# design.net
KiCad netlist of a schematic drawn in EasyEDA Pro
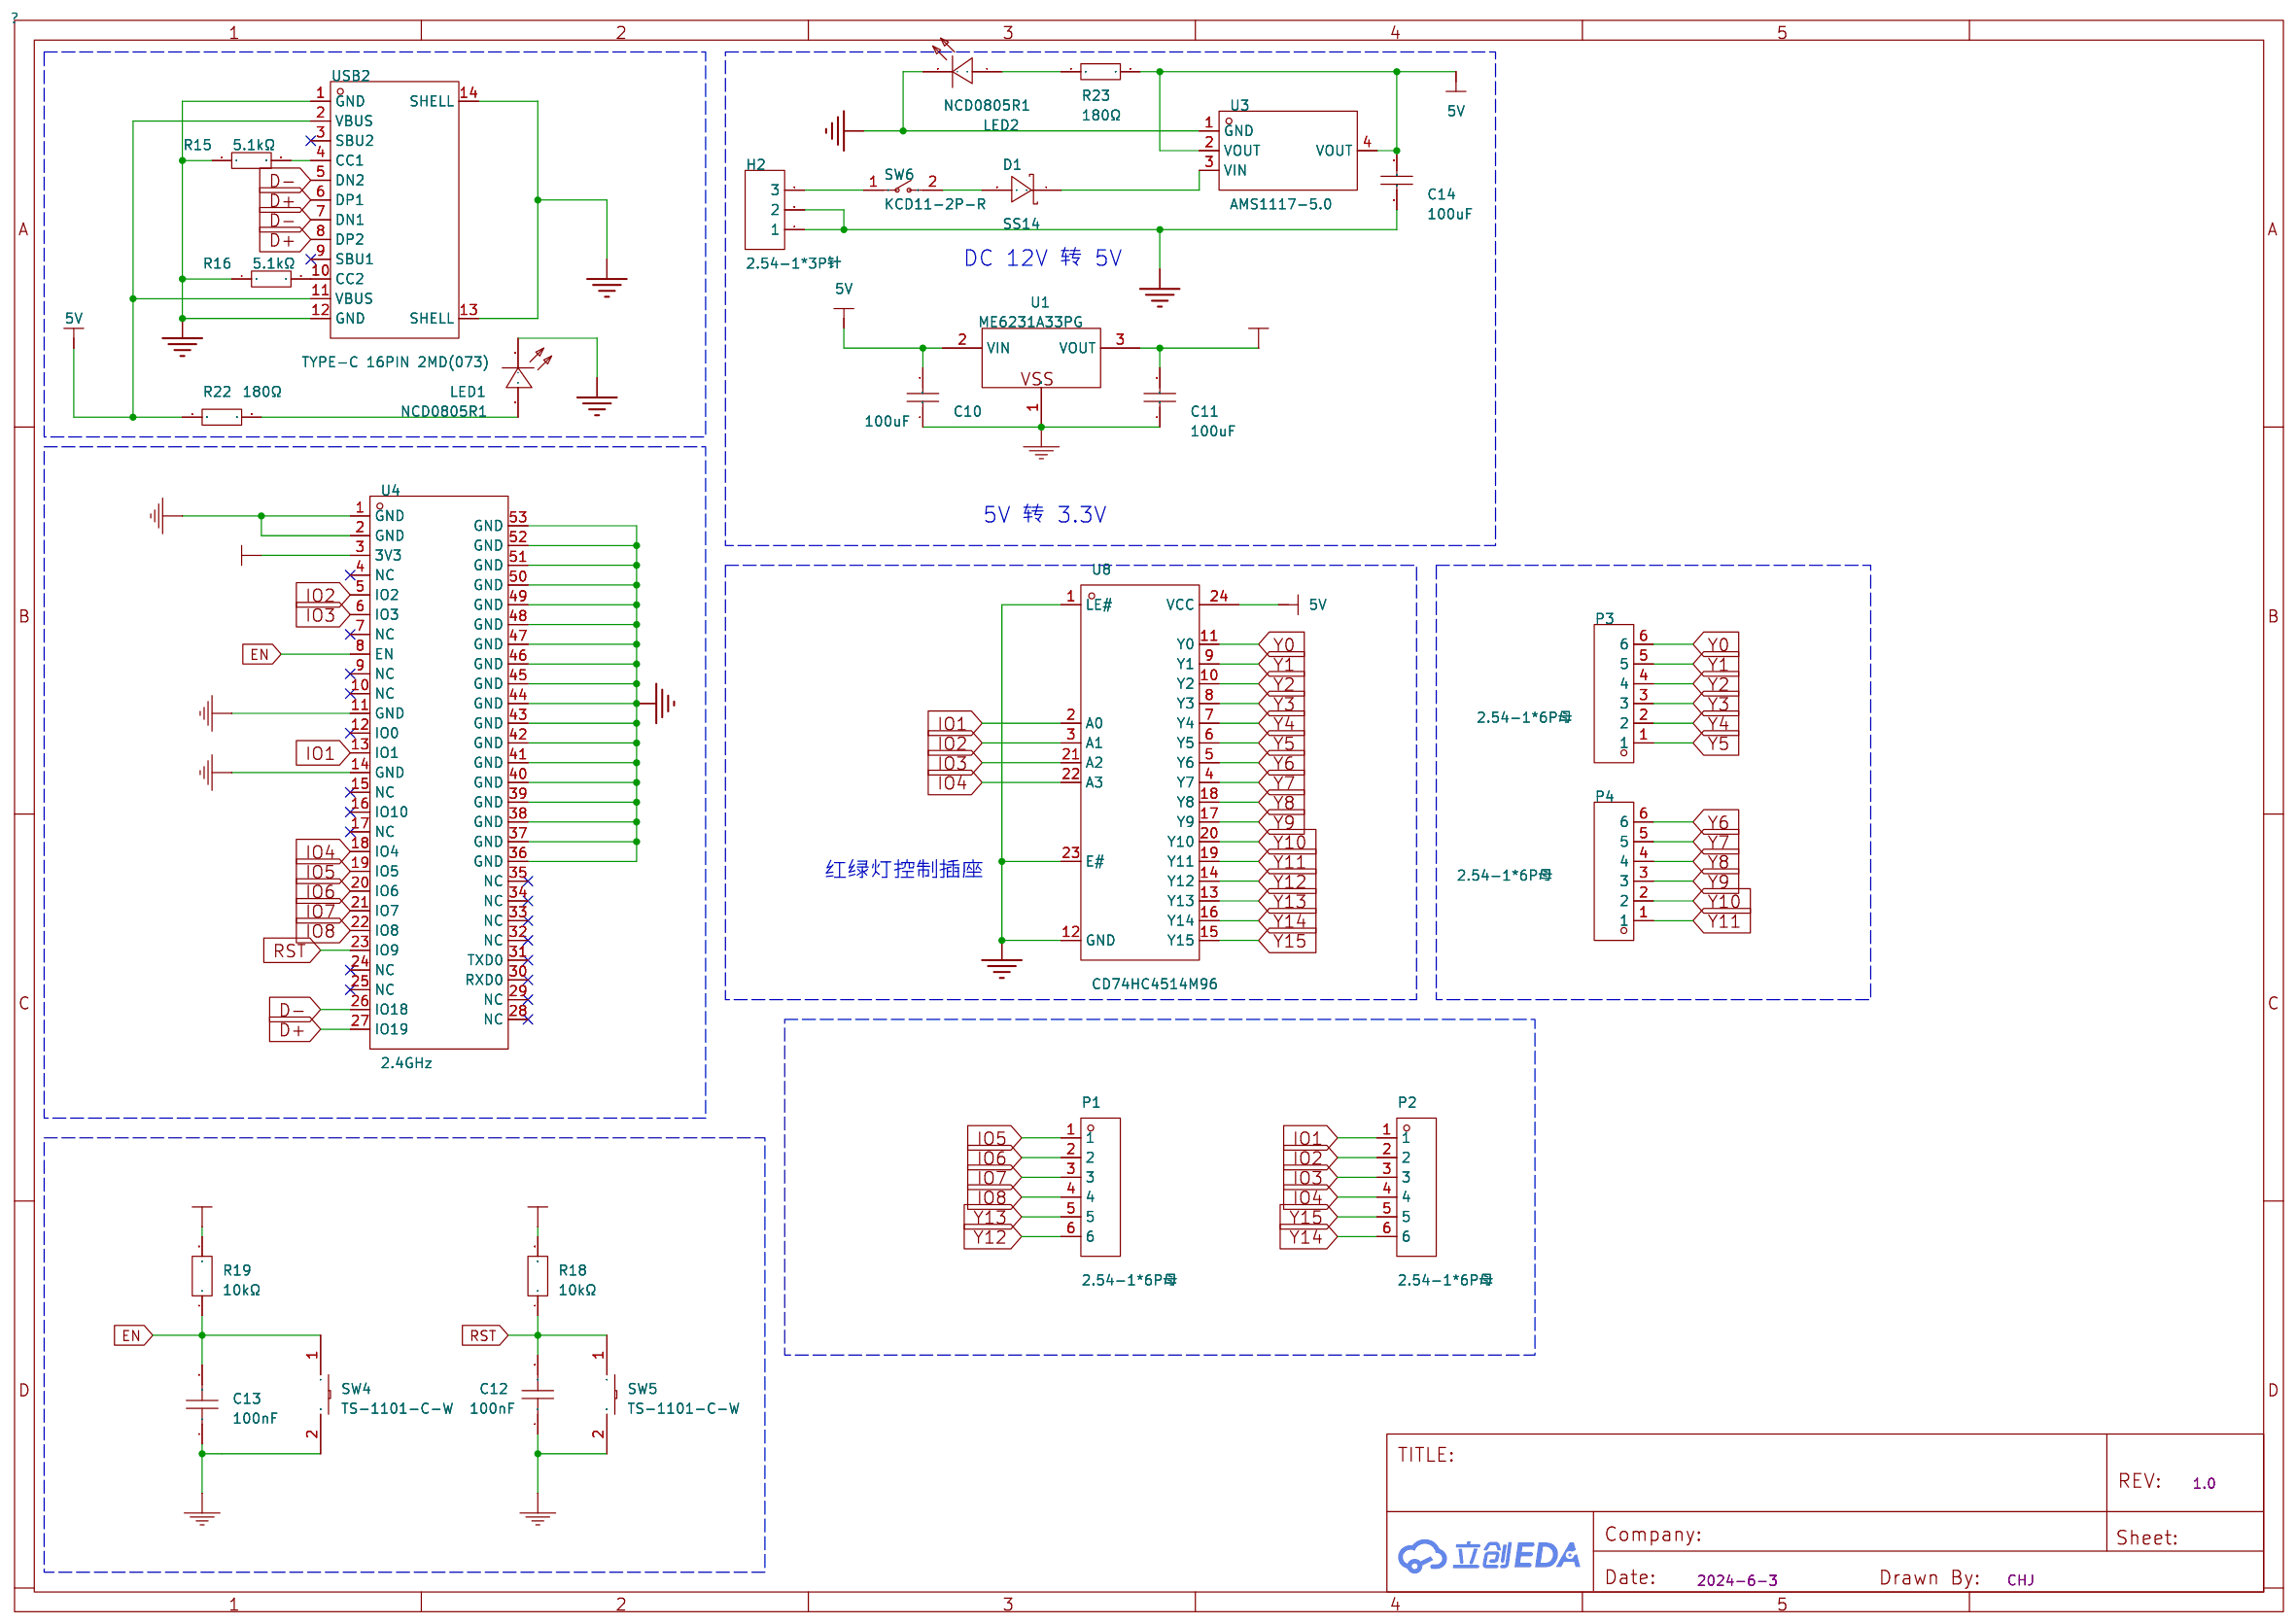
[diagram p0: schematic sheet]

(export (version "E")
  (design (tool "Eeschema 10.0.6"))
  (components
    (comp (ref "C10")
      (value "100uF")
      (footprint "easyedapro:C1206")
      (description "容值:100uF;精度:±20%;额定电压:6.3V;材质(温度系数):X5R;")
      (fields
        (field (name "Manufacturer Part") "CL31A107MQHNNNE")
        (field (name "Manufacturer") "SAMSUNG(三星)")
      )
      (libsource (lib "easyedapro") (part "CL31A107MQHNNNE"))
    )
    (comp (ref "C11")
      (value "100uF")
      (footprint "easyedapro:C1206")
      (description "容值:100uF;精度:±20%;额定电压:6.3V;材质(温度系数):X5R;")
      (fields
        (field (name "Manufacturer Part") "CL31A107MQHNNNE")
        (field (name "Manufacturer") "SAMSUNG(三星)")
      )
      (libsource (lib "easyedapro") (part "CL31A107MQHNNNE"))
    )
    (comp (ref "C12")
      (value "100nF")
      (footprint "easyedapro:C0603")
      (description "容值:100nF;精度:±10%;额定电压:50V;材质(温度系数):X7R;")
      (fields
        (field (name "Manufacturer Part") "CC0603KRX7R9BB104")
        (field (name "Manufacturer") "YAGEO(国巨)")
      )
      (libsource (lib "easyedapro") (part "CC0603KRX7R9BB104"))
    )
    (comp (ref "C13")
      (value "100nF")
      (footprint "easyedapro:C0603")
      (description "容值:100nF;精度:±10%;额定电压:50V;材质(温度系数):X7R;")
      (fields
        (field (name "Manufacturer Part") "CC0603KRX7R9BB104")
        (field (name "Manufacturer") "YAGEO(国巨)")
      )
      (libsource (lib "easyedapro") (part "CC0603KRX7R9BB104"))
    )
    (comp (ref "C14")
      (value "100uF")
      (footprint "easyedapro:C1206")
      (description "容值:100uF;精度:±20%;额定电压:6.3V;材质(温度系数):X5R;")
      (fields
        (field (name "Manufacturer Part") "CL31A107MQHNNNE")
        (field (name "Manufacturer") "SAMSUNG(三星)")
      )
      (libsource (lib "easyedapro") (part "CL31A107MQHNNNE"))
    )
    (comp (ref "D1")
      (value "SS14")
      (footprint "easyedapro:SMA_L4.2-W2.6-LS5.3-RD")
      (description "二极管配置:独立式;正向压降(Vf):550mV@1A;直流反向耐压(Vr):40V;平均整流电流(Io):1A;")
      (fields (field (name "Manufacturer") "MDD"))
      (libsource (lib "easyedapro") (part "SS14"))
    )
    (comp (ref "H2")
      (value "2.54-1*3P针")
      (footprint "easyedapro:HDR-TH_3P-P2.54-V-M-1")
      (fields (field (name "Manufacturer") "BOOMELE(博穆精密)"))
      (libsource (lib "easyedapro") (part "Header-Male-2.54_1x3"))
    )
    (comp (ref "LED1")
      (value "NCD0805R1")
      (footprint "easyedapro:LED0805-R-RD")
      (fields (field (name "Manufacturer") "国星光电"))
      (libsource (lib "easyedapro") (part "FC-2012HRK-620D"))
    )
    (comp (ref "LED2")
      (value "NCD0805R1")
      (footprint "easyedapro:LED0805-R-RD")
      (fields (field (name "Manufacturer") "国星光电"))
      (libsource (lib "easyedapro") (part "FC-2012HRK-620D"))
    )
    (comp (ref "P1")
      (value "2.54-1*6P母")
      (footprint "easyedapro:HDR-TH_6P-P2.54-V-F")
      (description "插孔结构:1x6P;间距:2.54mm;行距:-;安装类型:直插;排数:单排;总孔位数:6P;塑高:-;触头材质:-;触头镀层:-;")
      (fields (field (name "Manufacturer") "BOOMELE(博穆精密)"))
      (libsource (lib "easyedapro") (part "Header-Female-2.54_1x6"))
    )
    (comp (ref "P2")
      (value "2.54-1*6P母")
      (footprint "easyedapro:HDR-TH_6P-P2.54-V-F")
      (description "插孔结构:1x6P;间距:2.54mm;行距:-;安装类型:直插;排数:单排;总孔位数:6P;塑高:-;触头材质:-;触头镀层:-;")
      (fields (field (name "Manufacturer") "BOOMELE(博穆精密)"))
      (libsource (lib "easyedapro") (part "Header-Female-2.54_1x6"))
    )
    (comp (ref "P3")
      (value "2.54-1*6P母")
      (footprint "easyedapro:HDR-TH_6P-P2.54-V-F")
      (description "插孔结构:1x6P;间距:2.54mm;行距:-;安装类型:直插;排数:单排;总孔位数:6P;塑高:-;触头材质:-;触头镀层:-;")
      (fields (field (name "Manufacturer") "BOOMELE(博穆精密)"))
      (libsource (lib "easyedapro") (part "Header-Female-2.54_1x6"))
    )
    (comp (ref "P4")
      (value "2.54-1*6P母")
      (footprint "easyedapro:HDR-TH_6P-P2.54-V-F")
      (description "插孔结构:1x6P;间距:2.54mm;行距:-;安装类型:直插;排数:单排;总孔位数:6P;塑高:-;触头材质:-;触头镀层:-;")
      (fields (field (name "Manufacturer") "BOOMELE(博穆精密)"))
      (libsource (lib "easyedapro") (part "Header-Female-2.54_1x6"))
    )
    (comp (ref "R15")
      (value "5.1kΩ")
      (footprint "easyedapro:R0603")
      (description "电阻类型:厚膜电阻;阻值:5.1kΩ;精度:±1%;功率:100mW;最大工作电压:75V;温度系数:±100ppm/°C;")
      (fields
        (field (name "Manufacturer Part") "0603WAF5101T5E")
        (field (name "Manufacturer") "UNI-ROYAL(厚声)")
      )
      (libsource (lib "easyedapro") (part "0603WAF5101T5E"))
    )
    (comp (ref "R16")
      (value "5.1kΩ")
      (footprint "easyedapro:R0603")
      (description "电阻类型:厚膜电阻;阻值:5.1kΩ;精度:±1%;功率:100mW;最大工作电压:75V;温度系数:±100ppm/°C;")
      (fields
        (field (name "Manufacturer Part") "0603WAF5101T5E")
        (field (name "Manufacturer") "UNI-ROYAL(厚声)")
      )
      (libsource (lib "easyedapro") (part "0603WAF5101T5E"))
    )
    (comp (ref "R18")
      (value "10kΩ")
      (footprint "easyedapro:R0603")
      (description "电阻类型:厚膜电阻;阻值:10kΩ;精度:±5%;功率:100mW;最大工作电压:75V;温度系数:±100ppm/°C;")
      (fields (field (name "Manufacturer Part") "FRC0603J103TS") (field (name "Manufacturer") "FOJAN(富捷)"))
      (libsource (lib "easyedapro") (part "FRC0603J103TS"))
    )
    (comp (ref "R19")
      (value "10kΩ")
      (footprint "easyedapro:R0603")
      (description "电阻类型:厚膜电阻;阻值:10kΩ;精度:±5%;功率:100mW;最大工作电压:75V;温度系数:±100ppm/°C;")
      (fields (field (name "Manufacturer Part") "FRC0603J103TS") (field (name "Manufacturer") "FOJAN(富捷)"))
      (libsource (lib "easyedapro") (part "FRC0603J103TS"))
    )
    (comp (ref "R22")
      (value "180Ω")
      (footprint "easyedapro:R0805")
      (description "电阻类型:厚膜电阻;阻值:180Ω;精度:±1%;功率:125mW;最大工作电压:150V;温度系数:±100ppm/°C;")
      (fields
        (field (name "Manufacturer Part") "0805W8F1800T5E")
        (field (name "Manufacturer") "UNI-ROYAL(厚声)")
      )
      (libsource (lib "easyedapro") (part "0805W8F1800T5E"))
    )
    (comp (ref "R23")
      (value "180Ω")
      (footprint "easyedapro:R0805")
      (description "电阻类型:厚膜电阻;阻值:180Ω;精度:±1%;功率:125mW;最大工作电压:150V;温度系数:±100ppm/°C;")
      (fields
        (field (name "Manufacturer Part") "0805W8F1800T5E")
        (field (name "Manufacturer") "UNI-ROYAL(厚声)")
      )
      (libsource (lib "easyedapro") (part "0805W8F1800T5E"))
    )
    (comp (ref "SW4")
      (value "TS-1101-C-W")
      (footprint "easyedapro:SW-SMD_L6.0-W3.3-LS8.0")
      (fields (field (name "Manufacturer") "XKB Connectivity(中国星坤)"))
      (libsource (lib "easyedapro") (part "TS-1101-C-W"))
    )
    (comp (ref "SW5")
      (value "TS-1101-C-W")
      (footprint "easyedapro:SW-SMD_L6.0-W3.3-LS8.0")
      (fields (field (name "Manufacturer") "XKB Connectivity(中国星坤)"))
      (libsource (lib "easyedapro") (part "TS-1101-C-W"))
    )
    (comp (ref "SW6")
      (value "KCD11-2P-R")
      (footprint "easyedapro:SW-TH_2P-L15.0-W10.5-P5.00_KCD11-2P-R")
      (description "带灯:无;引脚样式:焊片;额定电流:3A;额定电压(AC):250V;额定电压(DC):-;电路结构:单刀单掷;机械寿命:1万次;")
      (fields (field (name "Manufacturer") "SHOU HAN(首韩)"))
      (libsource (lib "easyedapro") (part "KCD11-2P-R"))
    )
    (comp (ref "U1")
      (value "ME6231A33PG")
      (footprint "easyedapro:SOT-89-3_L4.5-W2.5-P1.50-LS4.2-BR")
      (fields (field (name "Manufacturer") "MICRONE(南京微盟)"))
      (libsource (lib "easyedapro") (part "ME6231A33PG"))
    )
    (comp (ref "U3")
      (value "AMS1117-5.0")
      (footprint "easyedapro:SOT-223_L6.5-W3.5-P2.30-LS7.0-BR")
      (description "输出类型:固定;最大输入电压:12V;输出电压:5V;最大输出电流:1A;电源纹波抑制比(PSRR):68dB@(120Hz);输出极性:正极;")
      (fields (field (name "Manufacturer") "AMS"))
      (libsource (lib "easyedapro") (part "AMS1117-5.0"))
    )
    (comp (ref "U4")
      (value "2.4GHz")
      (footprint "easyedapro:WIFIM-SMD_ESP32-C3-MINI-1")
      (description "核心处理器:-;频率:2.4GHz;天线形式:板载PCB天线;发射功率:20.5dBm;接收灵敏度:-96dBm;")
      (fields
        (field (name "Manufacturer Part") "ESP32-C3-MINI-1-H4")
        (field (name "Manufacturer") "ESPRESSIF(乐鑫)")
      )
      (libsource (lib "easyedapro") (part "ESP32-C3-MINI-1-H4(4MB)"))
    )
    (comp (ref "U8")
      (value "CD74HC4514M96")
      (footprint "easyedapro:SOIC-24_L15.4-W7.5-P1.27-LS10.3-BL")
      (description "供电电压:2V~6V;灌电流(IOL):5.2mA;拉电流(IOH):5.2mA;")
      (fields (field (name "Manufacturer") "TI(德州仪器)"))
      (libsource (lib "easyedapro") (part "CD74HC4514M96"))
    )
    (comp (ref "USB2")
      (value "TYPE-C 16PIN 2MD(073)")
      (footprint "easyedapro:USB-C-SMD_TYPE-C-6PIN-2MD-073")
      (description "连接器类型:Type-C;标准:-;公母:母;端口数量:1;触点数量:16P;安装方式:卧贴;额定电流 - 电源:5A;工作温度范围:-25°C~+85°C;")
      (fields (field (name "Manufacturer") "SHOU HAN(首韩)"))
      (libsource (lib "easyedapro") (part "TYPE-C 16PIN 2MD(073)"))
    )
  )
  (nets
    (net (code "1") (name "3.3V") (class "Default")
      (node (ref "C11") (pin "2") (pinfunction "2_2") (pintype "input"))
      (node (ref "R18") (pin "2") (pinfunction "2_2") (pintype "unspecified"))
      (node (ref "R19") (pin "2") (pinfunction "2_2") (pintype "unspecified"))
      (node (ref "U1") (pin "3") (pinfunction "VOUT_3") (pintype "unspecified"))
      (node (ref "U4") (pin "3") (pinfunction "3V3_3") (pintype "unspecified"))
    )
    (net (code "2") (name "5V") (class "Default")
      (node (ref "C10") (pin "2") (pinfunction "2_2") (pintype "input"))
      (node (ref "C14") (pin "2") (pinfunction "2_2") (pintype "input"))
      (node (ref "R22") (pin "1") (pinfunction "1_1") (pintype "input"))
      (node (ref "R23") (pin "2") (pinfunction "2_2") (pintype "input"))
      (node (ref "U1") (pin "2") (pinfunction "VIN_2") (pintype "unspecified"))
      (node (ref "U3") (pin "2") (pinfunction "VOUT_2") (pintype "unspecified"))
      (node (ref "U3") (pin "4") (pinfunction "VOUT_4") (pintype "unspecified"))
      (node (ref "U8") (pin "24") (pinfunction "VCC_24") (pintype "input"))
      (node (ref "USB2") (pin "11") (pinfunction "VBUS_11") (pintype "unspecified"))
      (node (ref "USB2") (pin "2") (pinfunction "VBUS_2") (pintype "unspecified"))
    )
    (net (code "3") (name "D+") (class "Default")
      (node (ref "U4") (pin "27") (pinfunction "IO19_27") (pintype "unspecified"))
      (node (ref "USB2") (pin "6") (pinfunction "DP1_6") (pintype "unspecified"))
      (node (ref "USB2") (pin "8") (pinfunction "DP2_8") (pintype "unspecified"))
    )
    (net (code "4") (name "D-") (class "Default")
      (node (ref "U4") (pin "26") (pinfunction "IO18_26") (pintype "unspecified"))
      (node (ref "USB2") (pin "5") (pinfunction "DN2_5") (pintype "unspecified"))
      (node (ref "USB2") (pin "7") (pinfunction "DN1_7") (pintype "unspecified"))
    )
    (net (code "5") (name "EN") (class "Default")
      (node (ref "C13") (pin "2") (pinfunction "2_2") (pintype "unspecified"))
      (node (ref "R19") (pin "1") (pinfunction "1_1") (pintype "unspecified"))
      (node (ref "SW4") (pin "1") (pinfunction "1_1") (pintype "unspecified"))
      (node (ref "U4") (pin "8") (pinfunction "EN_8") (pintype "unspecified"))
    )
    (net (code "6") (name "GND") (class "Default")
      (node (ref "C10") (pin "1") (pinfunction "1_1") (pintype "input"))
      (node (ref "C11") (pin "1") (pinfunction "1_1") (pintype "input"))
      (node (ref "C12") (pin "1") (pinfunction "1_1") (pintype "unspecified"))
      (node (ref "C13") (pin "1") (pinfunction "1_1") (pintype "unspecified"))
      (node (ref "C14") (pin "1") (pinfunction "1_1") (pintype "input"))
      (node (ref "H2") (pin "1") (pinfunction "1_1") (pintype "input"))
      (node (ref "H2") (pin "2") (pinfunction "2_2") (pintype "input"))
      (node (ref "LED1") (pin "2") (pinfunction "-_2") (pintype "unspecified"))
      (node (ref "LED2") (pin "2") (pinfunction "-_2") (pintype "unspecified"))
      (node (ref "R15") (pin "1") (pinfunction "1_1") (pintype "input"))
      (node (ref "R16") (pin "1") (pinfunction "1_1") (pintype "input"))
      (node (ref "SW4") (pin "2") (pinfunction "2_2") (pintype "unspecified"))
      (node (ref "SW5") (pin "2") (pinfunction "2_2") (pintype "unspecified"))
      (node (ref "U1") (pin "1") (pinfunction "VSS_1") (pintype "unspecified"))
      (node (ref "U3") (pin "1") (pinfunction "GND_1") (pintype "unspecified"))
      (node (ref "U4") (pin "1") (pinfunction "GND_1") (pintype "unspecified"))
      (node (ref "U4") (pin "11") (pinfunction "GND_11") (pintype "unspecified"))
      (node (ref "U4") (pin "14") (pinfunction "GND_14") (pintype "unspecified"))
      (node (ref "U4") (pin "2") (pinfunction "GND_2") (pintype "unspecified"))
      (node (ref "U4") (pin "36") (pinfunction "GND_36") (pintype "unspecified"))
      (node (ref "U4") (pin "37") (pinfunction "GND_37") (pintype "unspecified"))
      (node (ref "U4") (pin "38") (pinfunction "GND_38") (pintype "unspecified"))
      (node (ref "U4") (pin "39") (pinfunction "GND_39") (pintype "unspecified"))
      (node (ref "U4") (pin "40") (pinfunction "GND_40") (pintype "unspecified"))
      (node (ref "U4") (pin "41") (pinfunction "GND_41") (pintype "unspecified"))
      (node (ref "U4") (pin "42") (pinfunction "GND_42") (pintype "unspecified"))
      (node (ref "U4") (pin "43") (pinfunction "GND_43") (pintype "unspecified"))
      (node (ref "U4") (pin "44") (pinfunction "GND_44") (pintype "unspecified"))
      (node (ref "U4") (pin "45") (pinfunction "GND_45") (pintype "unspecified"))
      (node (ref "U4") (pin "46") (pinfunction "GND_46") (pintype "unspecified"))
      (node (ref "U4") (pin "47") (pinfunction "GND_47") (pintype "unspecified"))
      (node (ref "U4") (pin "48") (pinfunction "GND_48") (pintype "unspecified"))
      (node (ref "U4") (pin "49") (pinfunction "GND_49") (pintype "unspecified"))
      (node (ref "U4") (pin "50") (pinfunction "GND_50") (pintype "unspecified"))
      (node (ref "U4") (pin "51") (pinfunction "GND_51") (pintype "unspecified"))
      (node (ref "U4") (pin "52") (pinfunction "GND_52") (pintype "unspecified"))
      (node (ref "U4") (pin "53") (pinfunction "GND_53") (pintype "unspecified"))
      (node (ref "U8") (pin "1") (pinfunction "LE#_1") (pintype "input"))
      (node (ref "U8") (pin "12") (pinfunction "GND_12") (pintype "input"))
      (node (ref "U8") (pin "23") (pinfunction "E#_23") (pintype "input"))
      (node (ref "USB2") (pin "1") (pinfunction "GND_1") (pintype "unspecified"))
      (node (ref "USB2") (pin "12") (pinfunction "GND_12") (pintype "unspecified"))
      (node (ref "USB2") (pin "13") (pinfunction "SHELL_13") (pintype "unspecified"))
      (node (ref "USB2") (pin "14") (pinfunction "SHELL_14") (pintype "unspecified"))
    )
    (net (code "7") (name "IO1") (class "Default")
      (node (ref "P2") (pin "1") (pinfunction "1_1") (pintype "unspecified"))
      (node (ref "U4") (pin "13") (pinfunction "IO1_13") (pintype "unspecified"))
      (node (ref "U8") (pin "2") (pinfunction "A0_2") (pintype "input"))
    )
    (net (code "8") (name "IO2") (class "Default")
      (node (ref "P2") (pin "2") (pinfunction "2_2") (pintype "unspecified"))
      (node (ref "U4") (pin "5") (pinfunction "IO2_5") (pintype "unspecified"))
      (node (ref "U8") (pin "3") (pinfunction "A1_3") (pintype "input"))
    )
    (net (code "9") (name "IO3") (class "Default")
      (node (ref "P2") (pin "3") (pinfunction "3_3") (pintype "unspecified"))
      (node (ref "U4") (pin "6") (pinfunction "IO3_6") (pintype "unspecified"))
      (node (ref "U8") (pin "21") (pinfunction "A2_21") (pintype "input"))
    )
    (net (code "10") (name "IO4") (class "Default")
      (node (ref "P2") (pin "4") (pinfunction "4_4") (pintype "unspecified"))
      (node (ref "U4") (pin "18") (pinfunction "IO4_18") (pintype "unspecified"))
      (node (ref "U8") (pin "22") (pinfunction "A3_22") (pintype "input"))
    )
    (net (code "11") (name "IO5") (class "Default")
      (node (ref "P1") (pin "1") (pinfunction "1_1") (pintype "unspecified"))
      (node (ref "U4") (pin "19") (pinfunction "IO5_19") (pintype "unspecified"))
    )
    (net (code "12") (name "IO6") (class "Default")
      (node (ref "P1") (pin "2") (pinfunction "2_2") (pintype "unspecified"))
      (node (ref "U4") (pin "20") (pinfunction "IO6_20") (pintype "unspecified"))
    )
    (net (code "13") (name "IO7") (class "Default")
      (node (ref "P1") (pin "3") (pinfunction "3_3") (pintype "unspecified"))
      (node (ref "U4") (pin "21") (pinfunction "IO7_21") (pintype "unspecified"))
    )
    (net (code "14") (name "IO8") (class "Default")
      (node (ref "P1") (pin "4") (pinfunction "4_4") (pintype "unspecified"))
      (node (ref "U4") (pin "22") (pinfunction "IO8_22") (pintype "unspecified"))
    )
    (net (code "15") (name "Net-(D1-A)") (class "Default")
      (node (ref "D1") (pin "2") (pinfunction "A_2") (pintype "unspecified"))
      (node (ref "SW6") (pin "2") (pinfunction "2_2") (pintype "unspecified"))
    )
    (net (code "16") (name "Net-(D1-K)") (class "Default")
      (node (ref "D1") (pin "1") (pinfunction "K_1") (pintype "unspecified"))
      (node (ref "U3") (pin "3") (pinfunction "VIN_3") (pintype "unspecified"))
    )
    (net (code "17") (name "Net-(H2-Pad3)") (class "Default")
      (node (ref "H2") (pin "3") (pinfunction "3_3") (pintype "input"))
      (node (ref "SW6") (pin "1") (pinfunction "1_1") (pintype "unspecified"))
    )
    (net (code "18") (name "Net-(LED1-+)") (class "Default")
      (node (ref "LED1") (pin "1") (pinfunction "+_1") (pintype "unspecified"))
      (node (ref "R22") (pin "2") (pinfunction "2_2") (pintype "input"))
    )
    (net (code "19") (name "Net-(LED2-+)") (class "Default")
      (node (ref "LED2") (pin "1") (pinfunction "+_1") (pintype "unspecified"))
      (node (ref "R23") (pin "1") (pinfunction "1_1") (pintype "input"))
    )
    (net (code "20") (name "Net-(USB2-CC1)") (class "Default")
      (node (ref "R15") (pin "2") (pinfunction "2_2") (pintype "input"))
      (node (ref "USB2") (pin "4") (pinfunction "CC1_4") (pintype "unspecified"))
    )
    (net (code "21") (name "Net-(USB2-CC2)") (class "Default")
      (node (ref "R16") (pin "2") (pinfunction "2_2") (pintype "input"))
      (node (ref "USB2") (pin "10") (pinfunction "CC2_10") (pintype "unspecified"))
    )
    (net (code "22") (name "RST") (class "Default")
      (node (ref "C12") (pin "2") (pinfunction "2_2") (pintype "unspecified"))
      (node (ref "R18") (pin "1") (pinfunction "1_1") (pintype "unspecified"))
      (node (ref "SW5") (pin "1") (pinfunction "1_1") (pintype "unspecified"))
      (node (ref "U4") (pin "23") (pinfunction "IO9_23") (pintype "unspecified"))
    )
    (net (code "23") (name "Y0") (class "Default")
      (node (ref "P3") (pin "6") (pinfunction "6_6") (pintype "unspecified"))
      (node (ref "U8") (pin "11") (pinfunction "Y0_11") (pintype "output"))
    )
    (net (code "24") (name "Y1") (class "Default")
      (node (ref "P3") (pin "5") (pinfunction "5_5") (pintype "unspecified"))
      (node (ref "U8") (pin "9") (pinfunction "Y1_9") (pintype "output"))
    )
    (net (code "25") (name "Y2") (class "Default")
      (node (ref "P3") (pin "4") (pinfunction "4_4") (pintype "unspecified"))
      (node (ref "U8") (pin "10") (pinfunction "Y2_10") (pintype "output"))
    )
    (net (code "26") (name "Y3") (class "Default")
      (node (ref "P3") (pin "3") (pinfunction "3_3") (pintype "unspecified"))
      (node (ref "U8") (pin "8") (pinfunction "Y3_8") (pintype "output"))
    )
    (net (code "27") (name "Y4") (class "Default")
      (node (ref "P3") (pin "2") (pinfunction "2_2") (pintype "unspecified"))
      (node (ref "U8") (pin "7") (pinfunction "Y4_7") (pintype "output"))
    )
    (net (code "28") (name "Y5") (class "Default")
      (node (ref "P3") (pin "1") (pinfunction "1_1") (pintype "unspecified"))
      (node (ref "U8") (pin "6") (pinfunction "Y5_6") (pintype "output"))
    )
    (net (code "29") (name "Y6") (class "Default")
      (node (ref "P4") (pin "6") (pinfunction "6_6") (pintype "unspecified"))
      (node (ref "U8") (pin "5") (pinfunction "Y6_5") (pintype "output"))
    )
    (net (code "30") (name "Y7") (class "Default")
      (node (ref "P4") (pin "5") (pinfunction "5_5") (pintype "unspecified"))
      (node (ref "U8") (pin "4") (pinfunction "Y7_4") (pintype "output"))
    )
    (net (code "31") (name "Y8") (class "Default")
      (node (ref "P4") (pin "4") (pinfunction "4_4") (pintype "unspecified"))
      (node (ref "U8") (pin "18") (pinfunction "Y8_18") (pintype "output"))
    )
    (net (code "32") (name "Y9") (class "Default")
      (node (ref "P4") (pin "3") (pinfunction "3_3") (pintype "unspecified"))
      (node (ref "U8") (pin "17") (pinfunction "Y9_17") (pintype "output"))
    )
    (net (code "33") (name "Y10") (class "Default")
      (node (ref "P4") (pin "2") (pinfunction "2_2") (pintype "unspecified"))
      (node (ref "U8") (pin "20") (pinfunction "Y10_20") (pintype "output"))
    )
    (net (code "34") (name "Y11") (class "Default")
      (node (ref "P4") (pin "1") (pinfunction "1_1") (pintype "unspecified"))
      (node (ref "U8") (pin "19") (pinfunction "Y11_19") (pintype "output"))
    )
    (net (code "35") (name "Y12") (class "Default")
      (node (ref "P1") (pin "6") (pinfunction "6_6") (pintype "unspecified"))
      (node (ref "U8") (pin "14") (pinfunction "Y12_14") (pintype "output"))
    )
    (net (code "36") (name "Y13") (class "Default")
      (node (ref "P1") (pin "5") (pinfunction "5_5") (pintype "unspecified"))
      (node (ref "U8") (pin "13") (pinfunction "Y13_13") (pintype "output"))
    )
    (net (code "37") (name "Y14") (class "Default")
      (node (ref "P2") (pin "6") (pinfunction "6_6") (pintype "unspecified"))
      (node (ref "U8") (pin "16") (pinfunction "Y14_16") (pintype "output"))
    )
    (net (code "38") (name "Y15") (class "Default")
      (node (ref "P2") (pin "5") (pinfunction "5_5") (pintype "unspecified"))
      (node (ref "U8") (pin "15") (pinfunction "Y15_15") (pintype "output"))
    )
    (net (code "39") (name "unconnected-(U4-IO0-Pad12)") (class "Default")
      (node (ref "U4") (pin "12") (pinfunction "IO0_12") (pintype "unspecified+no_connect"))
    )
    (net (code "40") (name "unconnected-(U4-IO10-Pad16)") (class "Default")
      (node (ref "U4") (pin "16") (pinfunction "IO10_16") (pintype "unspecified+no_connect"))
    )
    (net (code "41") (name "unconnected-(U4-NC-Pad4)") (class "Default")
      (node (ref "U4") (pin "4") (pinfunction "NC_4") (pintype "unspecified+no_connect"))
    )
    (net (code "42") (name "unconnected-(U4-NC-Pad7)") (class "Default")
      (node (ref "U4") (pin "7") (pinfunction "NC_7") (pintype "unspecified+no_connect"))
    )
    (net (code "43") (name "unconnected-(U4-NC-Pad9)") (class "Default")
      (node (ref "U4") (pin "9") (pinfunction "NC_9") (pintype "unspecified+no_connect"))
    )
    (net (code "44") (name "unconnected-(U4-NC-Pad10)") (class "Default")
      (node (ref "U4") (pin "10") (pinfunction "NC_10") (pintype "unspecified+no_connect"))
    )
    (net (code "45") (name "unconnected-(U4-NC-Pad15)") (class "Default")
      (node (ref "U4") (pin "15") (pinfunction "NC_15") (pintype "unspecified+no_connect"))
    )
    (net (code "46") (name "unconnected-(U4-NC-Pad17)") (class "Default")
      (node (ref "U4") (pin "17") (pinfunction "NC_17") (pintype "unspecified+no_connect"))
    )
    (net (code "47") (name "unconnected-(U4-NC-Pad24)") (class "Default")
      (node (ref "U4") (pin "24") (pinfunction "NC_24") (pintype "unspecified+no_connect"))
    )
    (net (code "48") (name "unconnected-(U4-NC-Pad25)") (class "Default")
      (node (ref "U4") (pin "25") (pinfunction "NC_25") (pintype "unspecified+no_connect"))
    )
    (net (code "49") (name "unconnected-(U4-NC-Pad28)") (class "Default")
      (node (ref "U4") (pin "28") (pinfunction "NC_28") (pintype "unspecified+no_connect"))
    )
    (net (code "50") (name "unconnected-(U4-NC-Pad29)") (class "Default")
      (node (ref "U4") (pin "29") (pinfunction "NC_29") (pintype "unspecified+no_connect"))
    )
    (net (code "51") (name "unconnected-(U4-NC-Pad32)") (class "Default")
      (node (ref "U4") (pin "32") (pinfunction "NC_32") (pintype "unspecified+no_connect"))
    )
    (net (code "52") (name "unconnected-(U4-NC-Pad33)") (class "Default")
      (node (ref "U4") (pin "33") (pinfunction "NC_33") (pintype "unspecified+no_connect"))
    )
    (net (code "53") (name "unconnected-(U4-NC-Pad34)") (class "Default")
      (node (ref "U4") (pin "34") (pinfunction "NC_34") (pintype "unspecified+no_connect"))
    )
    (net (code "54") (name "unconnected-(U4-NC-Pad35)") (class "Default")
      (node (ref "U4") (pin "35") (pinfunction "NC_35") (pintype "unspecified+no_connect"))
    )
    (net (code "55") (name "unconnected-(U4-RXD0-Pad30)") (class "Default")
      (node (ref "U4") (pin "30") (pinfunction "RXD0_30") (pintype "unspecified+no_connect"))
    )
    (net (code "56") (name "unconnected-(U4-TXD0-Pad31)") (class "Default")
      (node (ref "U4") (pin "31") (pinfunction "TXD0_31") (pintype "unspecified+no_connect"))
    )
    (net (code "57") (name "unconnected-(USB2-SBU1-Pad9)") (class "Default")
      (node (ref "USB2") (pin "9") (pinfunction "SBU1_9") (pintype "unspecified+no_connect"))
    )
    (net (code "58") (name "unconnected-(USB2-SBU2-Pad3)") (class "Default")
      (node (ref "USB2") (pin "3") (pinfunction "SBU2_3") (pintype "unspecified+no_connect"))
    )
  )
)
